# TIDA-010933-DCDC-OpAmp.net
KiCad netlist of a schematic drawn in Altium Designer
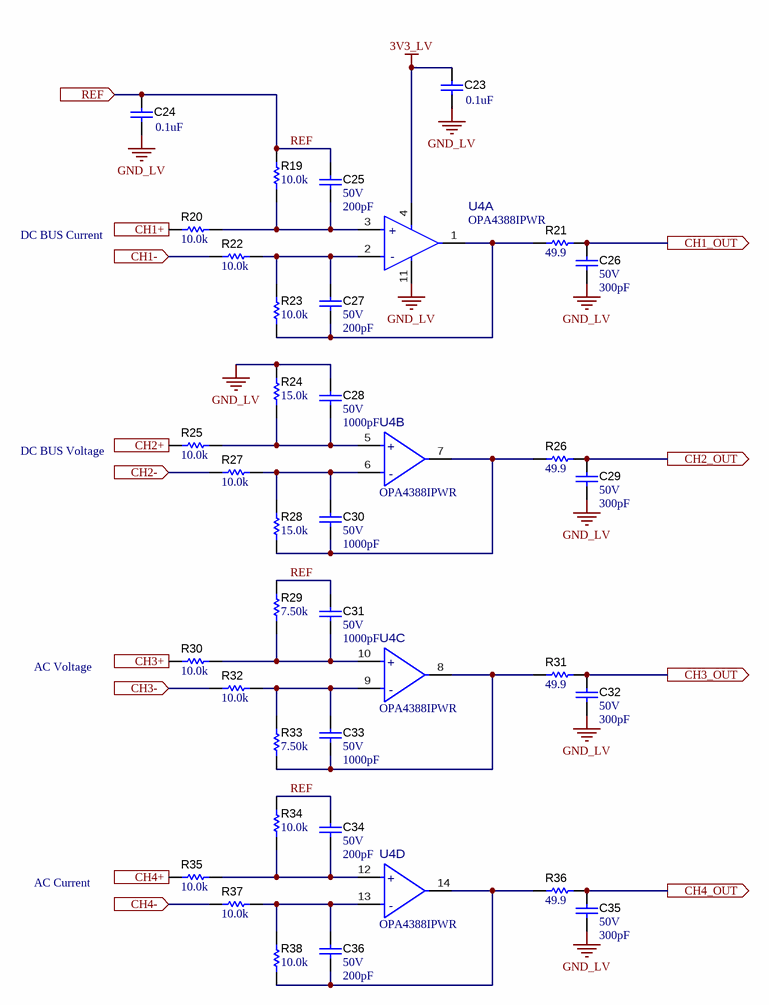
[diagram p0: TIDA-010933-DCDC-OpAmp.SchDoc]

(export (version "E")
  (design (tool "Eeschema 10.0.6"))
  (components
    (comp (ref "C23")
      (value "GRM155R71E104KE14D")
      (footprint "0402")
      (description "CAP, CERM, 0.1 uF, 25 V, +/- 10%, X7R, 0402")
      (fields
        (field (name "MANUFACTURER") "MuRata")
        (field (name "VALUEDISPLAYED") "0.1uF")
        (field (name "PUBLISHER") "Texas Instruments")
      )
      (libsource (lib "Altium Vault - TI") (part "Capacitor"))
    )
    (comp (ref "C24")
      (value "GRM155R71E104KE14D")
      (footprint "0402")
      (description "CAP, CERM, 0.1 uF, 25 V, +/- 10%, X7R, 0402")
      (fields
        (field (name "MANUFACTURER") "MuRata")
        (field (name "VALUEDISPLAYED") "0.1uF")
        (field (name "PUBLISHER") "Texas Instruments")
      )
      (libsource (lib "Altium Vault - TI") (part "Capacitor"))
    )
    (comp (ref "C25")
      (value "GRM1555C1H201JA01D")
      (footprint "0402")
      (description "CAP, CERM, 200 pF, 50 V, +/- 5%, C0G/NP0, 0402")
      (fields
        (field (name "MANUFACTURER") "MuRata")
        (field (name "VDC_V") "50V")
        (field (name "VALUEDISPLAYED") "200pF")
        (field (name "PUBLISHER") "Texas Instruments")
      )
      (libsource (lib "Altium Vault - TI") (part "Capacitor"))
    )
    (comp (ref "C26")
      (value "GRM1555C1H301JA01D")
      (footprint "0402")
      (description "CAP, CERM, 300 pF, 50 V, +/- 5%, C0G/NP0, 0402")
      (fields
        (field (name "MANUFACTURER") "MuRata")
        (field (name "VDC_V") "50V")
        (field (name "VALUEDISPLAYED") "300pF")
        (field (name "PUBLISHER") "Texas Instruments")
      )
      (libsource (lib "Altium Vault - TI") (part "Capacitor"))
    )
    (comp (ref "C27")
      (value "GRM1555C1H201JA01D")
      (footprint "0402")
      (description "CAP, CERM, 200 pF, 50 V, +/- 5%, C0G/NP0, 0402")
      (fields
        (field (name "MANUFACTURER") "MuRata")
        (field (name "VDC_V") "50V")
        (field (name "VALUEDISPLAYED") "200pF")
        (field (name "PUBLISHER") "Texas Instruments")
      )
      (libsource (lib "Altium Vault - TI") (part "Capacitor"))
    )
    (comp (ref "C28")
      (value "GRM1555C1H102FA01D")
      (footprint "0402")
      (description "CAP, CERM, 1000 pF, 50 V, +/- 1%, C0G/NP0, 0402")
      (fields
        (field (name "MANUFACTURER") "MuRata")
        (field (name "VDC_V") "50V")
        (field (name "VALUEDISPLAYED") "1000pF")
        (field (name "PUBLISHER") "Texas Instruments")
      )
      (libsource (lib "Altium Vault - TI") (part "Capacitor"))
    )
    (comp (ref "C29")
      (value "GRM1555C1H301JA01D")
      (footprint "0402")
      (description "CAP, CERM, 300 pF, 50 V, +/- 5%, C0G/NP0, 0402")
      (fields
        (field (name "MANUFACTURER") "MuRata")
        (field (name "VDC_V") "50V")
        (field (name "VALUEDISPLAYED") "300pF")
        (field (name "PUBLISHER") "Texas Instruments")
      )
      (libsource (lib "Altium Vault - TI") (part "Capacitor"))
    )
    (comp (ref "C30")
      (value "GRM1555C1H102FA01D")
      (footprint "0402")
      (description "CAP, CERM, 1000 pF, 50 V, +/- 1%, C0G/NP0, 0402")
      (fields
        (field (name "MANUFACTURER") "MuRata")
        (field (name "VDC_V") "50V")
        (field (name "VALUEDISPLAYED") "1000pF")
        (field (name "PUBLISHER") "Texas Instruments")
      )
      (libsource (lib "Altium Vault - TI") (part "Capacitor"))
    )
    (comp (ref "C31")
      (value "GRM1555C1H102FA01D")
      (footprint "0402")
      (description "CAP, CERM, 1000 pF, 50 V, +/- 1%, C0G/NP0, 0402")
      (fields
        (field (name "MANUFACTURER") "MuRata")
        (field (name "VDC_V") "50V")
        (field (name "VALUEDISPLAYED") "1000pF")
        (field (name "PUBLISHER") "Texas Instruments")
      )
      (libsource (lib "Altium Vault - TI") (part "Capacitor"))
    )
    (comp (ref "C32")
      (value "GRM1555C1H301JA01D")
      (footprint "0402")
      (description "CAP, CERM, 300 pF, 50 V, +/- 5%, C0G/NP0, 0402")
      (fields
        (field (name "MANUFACTURER") "MuRata")
        (field (name "VDC_V") "50V")
        (field (name "VALUEDISPLAYED") "300pF")
        (field (name "PUBLISHER") "Texas Instruments")
      )
      (libsource (lib "Altium Vault - TI") (part "Capacitor"))
    )
    (comp (ref "C33")
      (value "GRM1555C1H102FA01D")
      (footprint "0402")
      (description "CAP, CERM, 1000 pF, 50 V, +/- 1%, C0G/NP0, 0402")
      (fields
        (field (name "MANUFACTURER") "MuRata")
        (field (name "VDC_V") "50V")
        (field (name "VALUEDISPLAYED") "1000pF")
        (field (name "PUBLISHER") "Texas Instruments")
      )
      (libsource (lib "Altium Vault - TI") (part "Capacitor"))
    )
    (comp (ref "C34")
      (value "GRM1555C1H201JA01D")
      (footprint "0402")
      (description "CAP, CERM, 200 pF, 50 V, +/- 5%, C0G/NP0, 0402")
      (fields
        (field (name "MANUFACTURER") "MuRata")
        (field (name "VDC_V") "50V")
        (field (name "VALUEDISPLAYED") "200pF")
        (field (name "PUBLISHER") "Texas Instruments")
      )
      (libsource (lib "Altium Vault - TI") (part "Capacitor"))
    )
    (comp (ref "C35")
      (value "GRM1555C1H301JA01D")
      (footprint "0402")
      (description "CAP, CERM, 300 pF, 50 V, +/- 5%, C0G/NP0, 0402")
      (fields
        (field (name "MANUFACTURER") "MuRata")
        (field (name "VDC_V") "50V")
        (field (name "VALUEDISPLAYED") "300pF")
        (field (name "PUBLISHER") "Texas Instruments")
      )
      (libsource (lib "Altium Vault - TI") (part "Capacitor"))
    )
    (comp (ref "C36")
      (value "GRM1555C1H201JA01D")
      (footprint "0402")
      (description "CAP, CERM, 200 pF, 50 V, +/- 5%, C0G/NP0, 0402")
      (fields
        (field (name "MANUFACTURER") "MuRata")
        (field (name "VDC_V") "50V")
        (field (name "VALUEDISPLAYED") "200pF")
        (field (name "PUBLISHER") "Texas Instruments")
      )
      (libsource (lib "Altium Vault - TI") (part "Capacitor"))
    )
    (comp (ref "R19")
      (value "RT0402BRD0710KL")
      (footprint "0402")
      (description "RES, 10.0 k, .1%, .0625 W, 0402")
      (fields
        (field (name "MANUFACTURER") "Yageo America")
        (field (name "VALUEDISPLAYED") "10.0k")
        (field (name "PUBLISHER") "Texas Instruments")
      )
      (libsource (lib "Altium Vault - TI") (part "Resistor"))
    )
    (comp (ref "R20")
      (value "RT0402BRD0710KL")
      (footprint "0402")
      (description "RES, 10.0 k, .1%, .0625 W, 0402")
      (fields
        (field (name "MANUFACTURER") "Yageo America")
        (field (name "VALUEDISPLAYED") "10.0k")
        (field (name "PUBLISHER") "Texas Instruments")
      )
      (libsource (lib "Altium Vault - TI") (part "Resistor"))
    )
    (comp (ref "R21")
      (value "RC0402FR-0749R9L")
      (footprint "0402")
      (description "RES, 49.9, 1%, 0.063 W, 0402")
      (fields
        (field (name "MANUFACTURER") "Yageo America")
        (field (name "VALUEDISPLAYED") "49.9")
        (field (name "PUBLISHER") "Texas Instruments")
      )
      (libsource (lib "Altium Vault - TI") (part "Resistor"))
    )
    (comp (ref "R22")
      (value "RT0402BRD0710KL")
      (footprint "0402")
      (description "RES, 10.0 k, .1%, .0625 W, 0402")
      (fields
        (field (name "MANUFACTURER") "Yageo America")
        (field (name "VALUEDISPLAYED") "10.0k")
        (field (name "PUBLISHER") "Texas Instruments")
      )
      (libsource (lib "Altium Vault - TI") (part "Resistor"))
    )
    (comp (ref "R23")
      (value "RT0402BRD0710KL")
      (footprint "0402")
      (description "RES, 10.0 k, .1%, .0625 W, 0402")
      (fields
        (field (name "MANUFACTURER") "Yageo America")
        (field (name "VALUEDISPLAYED") "10.0k")
        (field (name "PUBLISHER") "Texas Instruments")
      )
      (libsource (lib "Altium Vault - TI") (part "Resistor"))
    )
    (comp (ref "R24")
      (value "ERA-2AEB153X")
      (footprint "0402")
      (description "RES, 15.0 k, .1%, .063 W, AEC-Q200 Grade 0, 0402")
      (fields
        (field (name "MANUFACTURER") "Panasonic")
        (field (name "VALUEDISPLAYED") "15.0k")
        (field (name "PUBLISHER") "Texas Instruments")
      )
      (libsource (lib "Altium Vault - TI") (part "Resistor"))
    )
    (comp (ref "R25")
      (value "RT0402BRD0710KL")
      (footprint "0402")
      (description "RES, 10.0 k, .1%, .0625 W, 0402")
      (fields
        (field (name "MANUFACTURER") "Yageo America")
        (field (name "VALUEDISPLAYED") "10.0k")
        (field (name "PUBLISHER") "Texas Instruments")
      )
      (libsource (lib "Altium Vault - TI") (part "Resistor"))
    )
    (comp (ref "R26")
      (value "RC0402FR-0749R9L")
      (footprint "0402")
      (description "RES, 49.9, 1%, 0.063 W, 0402")
      (fields
        (field (name "MANUFACTURER") "Yageo America")
        (field (name "VALUEDISPLAYED") "49.9")
        (field (name "PUBLISHER") "Texas Instruments")
      )
      (libsource (lib "Altium Vault - TI") (part "Resistor"))
    )
    (comp (ref "R27")
      (value "RT0402BRD0710KL")
      (footprint "0402")
      (description "RES, 10.0 k, .1%, .0625 W, 0402")
      (fields
        (field (name "MANUFACTURER") "Yageo America")
        (field (name "VALUEDISPLAYED") "10.0k")
        (field (name "PUBLISHER") "Texas Instruments")
      )
      (libsource (lib "Altium Vault - TI") (part "Resistor"))
    )
    (comp (ref "R28")
      (value "ERA-2AEB153X")
      (footprint "0402")
      (description "RES, 15.0 k, .1%, .063 W, AEC-Q200 Grade 0, 0402")
      (fields
        (field (name "MANUFACTURER") "Panasonic")
        (field (name "VALUEDISPLAYED") "15.0k")
        (field (name "PUBLISHER") "Texas Instruments")
      )
      (libsource (lib "Altium Vault - TI") (part "Resistor"))
    )
    (comp (ref "R29")
      (value "ERA-2AEB752X")
      (footprint "0402")
      (description "RES, 7.50 k, 0.1%, 0.063 W, AEC-Q200 Grade 0, 0402")
      (fields
        (field (name "MANUFACTURER") "Panasonic")
        (field (name "VALUEDISPLAYED") "7.50k")
        (field (name "PUBLISHER") "Texas Instruments")
      )
      (libsource (lib "Altium Vault - TI") (part "Resistor"))
    )
    (comp (ref "R30")
      (value "RT0402BRD0710KL")
      (footprint "0402")
      (description "RES, 10.0 k, .1%, .0625 W, 0402")
      (fields
        (field (name "MANUFACTURER") "Yageo America")
        (field (name "VALUEDISPLAYED") "10.0k")
        (field (name "PUBLISHER") "Texas Instruments")
      )
      (libsource (lib "Altium Vault - TI") (part "Resistor"))
    )
    (comp (ref "R31")
      (value "RC0402FR-0749R9L")
      (footprint "0402")
      (description "RES, 49.9, 1%, 0.063 W, 0402")
      (fields
        (field (name "MANUFACTURER") "Yageo America")
        (field (name "VALUEDISPLAYED") "49.9")
        (field (name "PUBLISHER") "Texas Instruments")
      )
      (libsource (lib "Altium Vault - TI") (part "Resistor"))
    )
    (comp (ref "R32")
      (value "RT0402BRD0710KL")
      (footprint "0402")
      (description "RES, 10.0 k, .1%, .0625 W, 0402")
      (fields
        (field (name "MANUFACTURER") "Yageo America")
        (field (name "VALUEDISPLAYED") "10.0k")
        (field (name "PUBLISHER") "Texas Instruments")
      )
      (libsource (lib "Altium Vault - TI") (part "Resistor"))
    )
    (comp (ref "R33")
      (value "ERA-2AEB752X")
      (footprint "0402")
      (description "RES, 7.50 k, 0.1%, 0.063 W, AEC-Q200 Grade 0, 0402")
      (fields
        (field (name "MANUFACTURER") "Panasonic")
        (field (name "VALUEDISPLAYED") "7.50k")
        (field (name "PUBLISHER") "Texas Instruments")
      )
      (libsource (lib "Altium Vault - TI") (part "Resistor"))
    )
    (comp (ref "R34")
      (value "RT0402BRD0710KL")
      (footprint "0402")
      (description "RES, 10.0 k, .1%, .0625 W, 0402")
      (fields
        (field (name "MANUFACTURER") "Yageo America")
        (field (name "VALUEDISPLAYED") "10.0k")
        (field (name "PUBLISHER") "Texas Instruments")
      )
      (libsource (lib "Altium Vault - TI") (part "Resistor"))
    )
    (comp (ref "R35")
      (value "RT0402BRD0710KL")
      (footprint "0402")
      (description "RES, 10.0 k, .1%, .0625 W, 0402")
      (fields
        (field (name "MANUFACTURER") "Yageo America")
        (field (name "VALUEDISPLAYED") "10.0k")
        (field (name "PUBLISHER") "Texas Instruments")
      )
      (libsource (lib "Altium Vault - TI") (part "Resistor"))
    )
    (comp (ref "R36")
      (value "RC0402FR-0749R9L")
      (footprint "0402")
      (description "RES, 49.9, 1%, 0.063 W, 0402")
      (fields
        (field (name "MANUFACTURER") "Yageo America")
        (field (name "VALUEDISPLAYED") "49.9")
        (field (name "PUBLISHER") "Texas Instruments")
      )
      (libsource (lib "Altium Vault - TI") (part "Resistor"))
    )
    (comp (ref "R37")
      (value "RT0402BRD0710KL")
      (footprint "0402")
      (description "RES, 10.0 k, .1%, .0625 W, 0402")
      (fields
        (field (name "MANUFACTURER") "Yageo America")
        (field (name "VALUEDISPLAYED") "10.0k")
        (field (name "PUBLISHER") "Texas Instruments")
      )
      (libsource (lib "Altium Vault - TI") (part "Resistor"))
    )
    (comp (ref "R38")
      (value "RT0402BRD0710KL")
      (footprint "0402")
      (description "RES, 10.0 k, .1%, .0625 W, 0402")
      (fields
        (field (name "MANUFACTURER") "Yageo America")
        (field (name "VALUEDISPLAYED") "10.0k")
        (field (name "PUBLISHER") "Texas Instruments")
      )
      (libsource (lib "Altium Vault - TI") (part "Resistor"))
    )
    (comp (ref "U4")
      (value "OPA4388IPWR")
      (footprint "PW0014A-MFG")
      (description "Zero-Drift Amplifier 4 Circuit Rail-to-Rail 14-TSSOP")
      (fields
        (field (name "MANUFACTURER") "Texas Instruments")
        (field (name "PARTNUMBER") "OPA4388IPWR")
        (field (name "DIGIKEY PART NUMBER") "296-OPA4388IPWRCT-ND")
      )
      (libsource (lib "Altium Vault - TI") (part "SYM-OPA4388IPWR"))
    )
  )
  (nets
    (net (code "1") (name "/CH1+") (class "Default")
      (node (ref "R20") (pin "1") (pinfunction "1_1") (pintype "passive"))
    )
    (net (code "2") (name "/CH1-") (class "Default")
      (node (ref "R22") (pin "1") (pinfunction "1_1") (pintype "passive"))
    )
    (net (code "3") (name "/CH1_OUT") (class "Default")
      (node (ref "C26") (pin "1") (pinfunction "1_1") (pintype "passive"))
      (node (ref "R21") (pin "2") (pinfunction "2_2") (pintype "passive"))
    )
    (net (code "4") (name "/CH2+") (class "Default")
      (node (ref "R25") (pin "2") (pinfunction "2_2") (pintype "passive"))
    )
    (net (code "5") (name "/CH2-") (class "Default")
      (node (ref "R27") (pin "2") (pinfunction "2_2") (pintype "passive"))
    )
    (net (code "6") (name "/CH2_OUT") (class "Default")
      (node (ref "C29") (pin "1") (pinfunction "1_1") (pintype "passive"))
      (node (ref "R26") (pin "2") (pinfunction "2_2") (pintype "passive"))
    )
    (net (code "7") (name "/CH3+") (class "Default")
      (node (ref "R30") (pin "2") (pinfunction "2_2") (pintype "passive"))
    )
    (net (code "8") (name "/CH3-") (class "Default")
      (node (ref "R32") (pin "2") (pinfunction "2_2") (pintype "passive"))
    )
    (net (code "9") (name "/CH3_OUT") (class "Default")
      (node (ref "C32") (pin "1") (pinfunction "1_1") (pintype "passive"))
      (node (ref "R31") (pin "2") (pinfunction "2_2") (pintype "passive"))
    )
    (net (code "10") (name "/CH4+") (class "Default")
      (node (ref "R35") (pin "2") (pinfunction "2_2") (pintype "passive"))
    )
    (net (code "11") (name "/CH4-") (class "Default")
      (node (ref "R37") (pin "1") (pinfunction "1_1") (pintype "passive"))
    )
    (net (code "12") (name "/CH4_OUT") (class "Default")
      (node (ref "C35") (pin "1") (pinfunction "1_1") (pintype "passive"))
      (node (ref "R36") (pin "2") (pinfunction "2_2") (pintype "passive"))
    )
    (net (code "13") (name "/REF") (class "Default")
      (node (ref "C24") (pin "1") (pinfunction "1_1") (pintype "passive"))
      (node (ref "C25") (pin "2") (pinfunction "2_2") (pintype "passive"))
      (node (ref "C31") (pin "1") (pinfunction "1_1") (pintype "passive"))
      (node (ref "C34") (pin "2") (pinfunction "2_2") (pintype "passive"))
      (node (ref "R19") (pin "2") (pinfunction "2_2") (pintype "passive"))
      (node (ref "R29") (pin "2") (pinfunction "2_2") (pintype "passive"))
      (node (ref "R34") (pin "1") (pinfunction "1_1") (pintype "passive"))
    )
    (net (code "14") (name "3V3_LV") (class "Default")
      (node (ref "C23") (pin "1") (pinfunction "1_1") (pintype "passive"))
      (node (ref "U4") (pin "4") (pinfunction "V+_4") (pintype "power_in"))
    )
    (net (code "15") (name "GND_LV") (class "Default")
      (node (ref "C23") (pin "2") (pinfunction "2_2") (pintype "passive"))
      (node (ref "C24") (pin "2") (pinfunction "2_2") (pintype "passive"))
      (node (ref "C26") (pin "2") (pinfunction "2_2") (pintype "passive"))
      (node (ref "C28") (pin "1") (pinfunction "1_1") (pintype "passive"))
      (node (ref "C29") (pin "2") (pinfunction "2_2") (pintype "passive"))
      (node (ref "C32") (pin "2") (pinfunction "2_2") (pintype "passive"))
      (node (ref "C35") (pin "2") (pinfunction "2_2") (pintype "passive"))
      (node (ref "R24") (pin "2") (pinfunction "2_2") (pintype "passive"))
      (node (ref "U4") (pin "11") (pinfunction "V-_11") (pintype "power_in"))
    )
    (net (code "16") (name "Net-(U4A-+IN_A)") (class "Default")
      (node (ref "C25") (pin "1") (pinfunction "1_1") (pintype "passive"))
      (node (ref "R19") (pin "1") (pinfunction "1_1") (pintype "passive"))
      (node (ref "R20") (pin "2") (pinfunction "2_2") (pintype "passive"))
      (node (ref "U4") (pin "3") (pinfunction "+IN_A_3") (pintype "tri_state"))
    )
    (net (code "17") (name "Net-(U4A--IN_A)") (class "Default")
      (node (ref "C27") (pin "2") (pinfunction "2_2") (pintype "passive"))
      (node (ref "R22") (pin "2") (pinfunction "2_2") (pintype "passive"))
      (node (ref "R23") (pin "2") (pinfunction "2_2") (pintype "passive"))
      (node (ref "U4") (pin "2") (pinfunction "-IN_A_2") (pintype "tri_state"))
    )
    (net (code "18") (name "Net-(U4A-OUT_A)") (class "Default")
      (node (ref "C27") (pin "1") (pinfunction "1_1") (pintype "passive"))
      (node (ref "R21") (pin "1") (pinfunction "1_1") (pintype "passive"))
      (node (ref "R23") (pin "1") (pinfunction "1_1") (pintype "passive"))
      (node (ref "U4") (pin "1") (pinfunction "OUT_A_1") (pintype "passive"))
    )
    (net (code "19") (name "Net-(U4B-+IN_B)") (class "Default")
      (node (ref "C28") (pin "2") (pinfunction "2_2") (pintype "passive"))
      (node (ref "R24") (pin "1") (pinfunction "1_1") (pintype "passive"))
      (node (ref "R25") (pin "1") (pinfunction "1_1") (pintype "passive"))
      (node (ref "U4") (pin "5") (pinfunction "+IN_B_5") (pintype "tri_state"))
    )
    (net (code "20") (name "Net-(U4B--IN_B)") (class "Default")
      (node (ref "C30") (pin "1") (pinfunction "1_1") (pintype "passive"))
      (node (ref "R27") (pin "1") (pinfunction "1_1") (pintype "passive"))
      (node (ref "R28") (pin "2") (pinfunction "2_2") (pintype "passive"))
      (node (ref "U4") (pin "6") (pinfunction "-IN_B_6") (pintype "tri_state"))
    )
    (net (code "21") (name "Net-(U4B-OUT_B)") (class "Default")
      (node (ref "C30") (pin "2") (pinfunction "2_2") (pintype "passive"))
      (node (ref "R26") (pin "1") (pinfunction "1_1") (pintype "passive"))
      (node (ref "R28") (pin "1") (pinfunction "1_1") (pintype "passive"))
      (node (ref "U4") (pin "7") (pinfunction "OUT_B_7") (pintype "passive"))
    )
    (net (code "22") (name "Net-(U4C-+IN_C)") (class "Default")
      (node (ref "C31") (pin "2") (pinfunction "2_2") (pintype "passive"))
      (node (ref "R29") (pin "1") (pinfunction "1_1") (pintype "passive"))
      (node (ref "R30") (pin "1") (pinfunction "1_1") (pintype "passive"))
      (node (ref "U4") (pin "10") (pinfunction "+IN_C_10") (pintype "tri_state"))
    )
    (net (code "23") (name "Net-(U4C--IN_C)") (class "Default")
      (node (ref "C33") (pin "1") (pinfunction "1_1") (pintype "passive"))
      (node (ref "R32") (pin "1") (pinfunction "1_1") (pintype "passive"))
      (node (ref "R33") (pin "2") (pinfunction "2_2") (pintype "passive"))
      (node (ref "U4") (pin "9") (pinfunction "-IN_C_9") (pintype "tri_state"))
    )
    (net (code "24") (name "Net-(U4C-OUT_C)") (class "Default")
      (node (ref "C33") (pin "2") (pinfunction "2_2") (pintype "passive"))
      (node (ref "R31") (pin "1") (pinfunction "1_1") (pintype "passive"))
      (node (ref "R33") (pin "1") (pinfunction "1_1") (pintype "passive"))
      (node (ref "U4") (pin "8") (pinfunction "OUT_C_8") (pintype "passive"))
    )
    (net (code "25") (name "Net-(U4D-+IN_D)") (class "Default")
      (node (ref "C34") (pin "1") (pinfunction "1_1") (pintype "passive"))
      (node (ref "R34") (pin "2") (pinfunction "2_2") (pintype "passive"))
      (node (ref "R35") (pin "1") (pinfunction "1_1") (pintype "passive"))
      (node (ref "U4") (pin "12") (pinfunction "+IN_D_12") (pintype "tri_state"))
    )
    (net (code "26") (name "Net-(U4D--IN_D)") (class "Default")
      (node (ref "C36") (pin "2") (pinfunction "2_2") (pintype "passive"))
      (node (ref "R37") (pin "2") (pinfunction "2_2") (pintype "passive"))
      (node (ref "R38") (pin "1") (pinfunction "1_1") (pintype "passive"))
      (node (ref "U4") (pin "13") (pinfunction "-IN_D_13") (pintype "tri_state"))
    )
    (net (code "27") (name "Net-(U4D-OUT_D)") (class "Default")
      (node (ref "C36") (pin "1") (pinfunction "1_1") (pintype "passive"))
      (node (ref "R36") (pin "1") (pinfunction "1_1") (pintype "passive"))
      (node (ref "R38") (pin "2") (pinfunction "2_2") (pintype "passive"))
      (node (ref "U4") (pin "14") (pinfunction "OUT_D_14") (pintype "passive"))
    )
  )
)
